# Central_MABOS.net
KiCad netlist of a schematic drawn in EAGLE
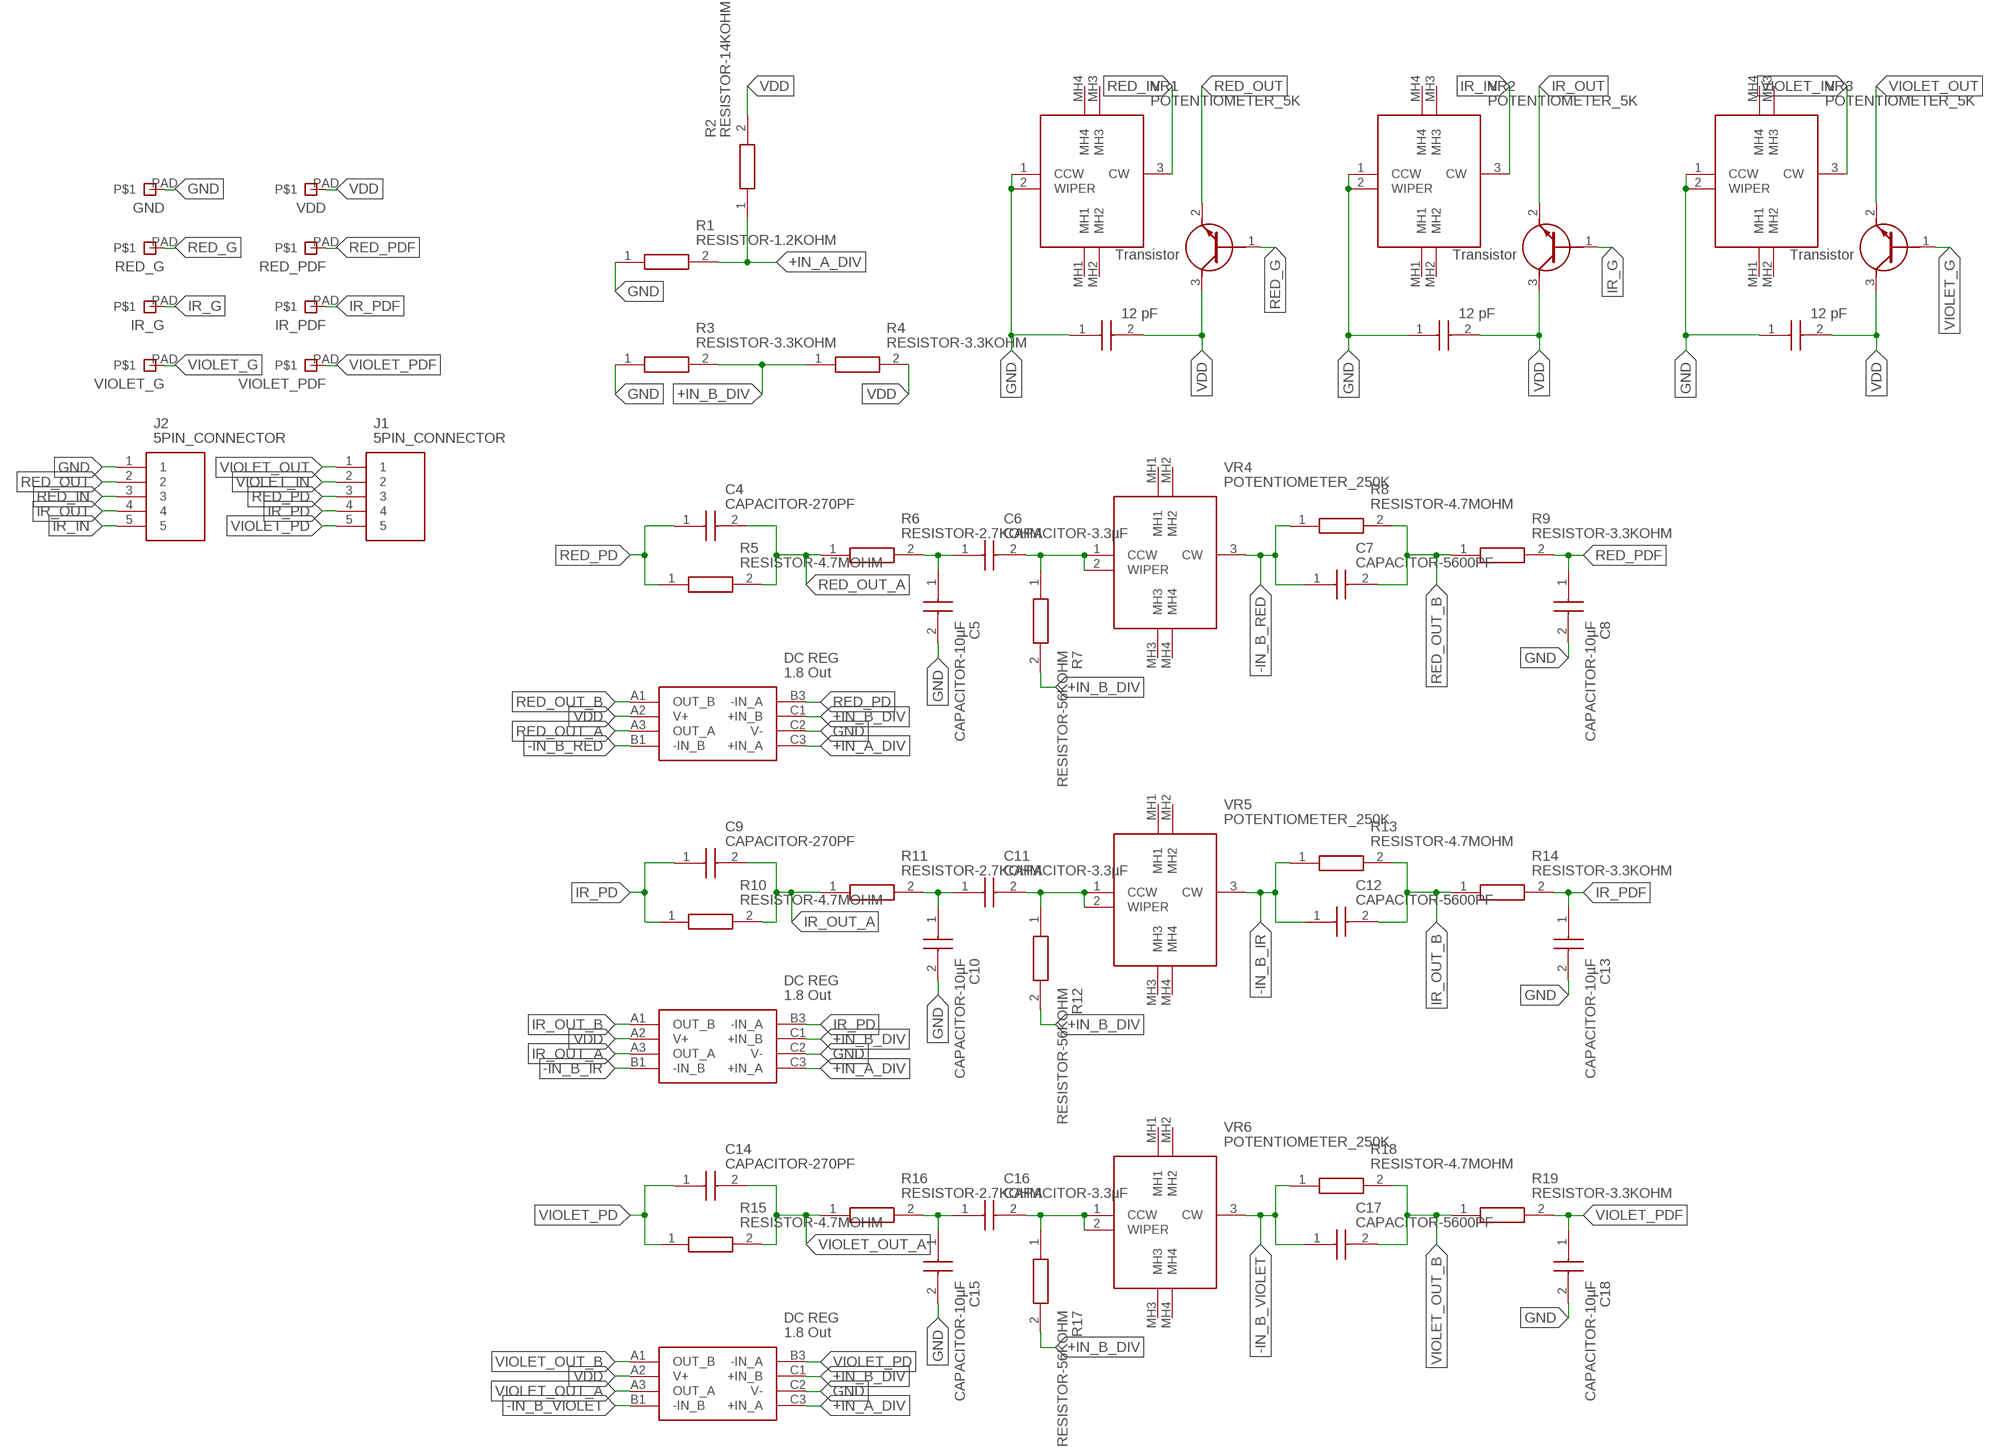
[diagram p0: schematic, sheet 1]

(export (version "E")
  (design (tool "Eeschema 10.0.6"))
  (components
    (comp (ref "C1")
      (value "CAPACITOR-12PF")
      (footprint "eagle-import:CAPC1005X55N")
      (fields
        (field (name "MANUFACTURER_PART_NUMBER") "C0402C120G3GACTU")
        (field (name "MOUSER_PART_NUMBER") "80-C0402C120G3G")
      )
      (libsource (lib "eagle-import") (part "CAPACITOR-12PF"))
    )
    (comp (ref "C2")
      (value "CAPACITOR-12PF")
      (footprint "eagle-import:CAPC1005X55N")
      (fields
        (field (name "MANUFACTURER_PART_NUMBER") "C0402C120G3GACTU")
        (field (name "MOUSER_PART_NUMBER") "80-C0402C120G3G")
      )
      (libsource (lib "eagle-import") (part "CAPACITOR-12PF"))
    )
    (comp (ref "C3")
      (value "CAPACITOR-12PF")
      (footprint "eagle-import:CAPC1005X55N")
      (fields
        (field (name "MANUFACTURER_PART_NUMBER") "C0402C120G3GACTU")
        (field (name "MOUSER_PART_NUMBER") "80-C0402C120G3G")
      )
      (libsource (lib "eagle-import") (part "CAPACITOR-12PF"))
    )
    (comp (ref "C4")
      (value "CAPACITOR-270PF")
      (footprint "eagle-import:CAPC1005X55N")
      (fields
        (field (name "MANUFACTURER_PART_NUMBER") "C0402C271G5GACTU")
        (field (name "MOUSER_PART_NUMBER") "80-C0402C271G5G")
      )
      (libsource (lib "eagle-import") (part "CAPACITOR-270PF"))
    )
    (comp (ref "C5")
      (value "CAPACITOR-10µF")
      (footprint "eagle-import:C0402")
      (fields
        (field (name "MANUFACTURER_PART_NUMBER") "C0402C106M9PACTU")
        (field (name "MOUSER_PART_NUMBER") "80-C0402C106M9P")
      )
      (libsource (lib "eagle-import") (part "CAPACITOR-10µF"))
    )
    (comp (ref "C6")
      (value "CAPACITOR-3.3µF")
      (footprint "eagle-import:C0402")
      (fields
        (field (name "MANUFACTURER_PART_NUMBER") "C0402C335M7PACTU")
        (field (name "MOUSER_PART_NUMBER") "80-C0402C335M7P")
      )
      (libsource (lib "eagle-import") (part "CAPACITOR-3.3µF"))
    )
    (comp (ref "C7")
      (value "CAPACITOR-5600PF")
      (footprint "eagle-import:CAPC1005X55N")
      (fields
        (field (name "MANUFACTURER_PART_NUMBER") "C0402C562J4RACTU")
        (field (name "MOUSER_PART_NUMBER") "80-C0402C562J4R")
      )
      (libsource (lib "eagle-import") (part "CAPACITOR-5600PF"))
    )
    (comp (ref "C8")
      (value "CAPACITOR-10µF")
      (footprint "eagle-import:C0402")
      (fields
        (field (name "MANUFACTURER_PART_NUMBER") "C0402C106M9PACTU")
        (field (name "MOUSER_PART_NUMBER") "80-C0402C106M9P")
      )
      (libsource (lib "eagle-import") (part "CAPACITOR-10µF"))
    )
    (comp (ref "C9")
      (value "CAPACITOR-270PF")
      (footprint "eagle-import:CAPC1005X55N")
      (fields
        (field (name "MANUFACTURER_PART_NUMBER") "C0402C271G5GACTU")
        (field (name "MOUSER_PART_NUMBER") "80-C0402C271G5G")
      )
      (libsource (lib "eagle-import") (part "CAPACITOR-270PF"))
    )
    (comp (ref "C10")
      (value "CAPACITOR-10µF")
      (footprint "eagle-import:C0402")
      (fields
        (field (name "MANUFACTURER_PART_NUMBER") "C0402C106M9PACTU")
        (field (name "MOUSER_PART_NUMBER") "80-C0402C106M9P")
      )
      (libsource (lib "eagle-import") (part "CAPACITOR-10µF"))
    )
    (comp (ref "C11")
      (value "CAPACITOR-3.3µF")
      (footprint "eagle-import:C0402")
      (fields
        (field (name "MANUFACTURER_PART_NUMBER") "C0402C335M7PACTU")
        (field (name "MOUSER_PART_NUMBER") "80-C0402C335M7P")
      )
      (libsource (lib "eagle-import") (part "CAPACITOR-3.3µF"))
    )
    (comp (ref "C12")
      (value "CAPACITOR-5600PF")
      (footprint "eagle-import:CAPC1005X55N")
      (fields
        (field (name "MANUFACTURER_PART_NUMBER") "C0402C562J4RACTU")
        (field (name "MOUSER_PART_NUMBER") "80-C0402C562J4R")
      )
      (libsource (lib "eagle-import") (part "CAPACITOR-5600PF"))
    )
    (comp (ref "C13")
      (value "CAPACITOR-10µF")
      (footprint "eagle-import:C0402")
      (fields
        (field (name "MANUFACTURER_PART_NUMBER") "C0402C106M9PACTU")
        (field (name "MOUSER_PART_NUMBER") "80-C0402C106M9P")
      )
      (libsource (lib "eagle-import") (part "CAPACITOR-10µF"))
    )
    (comp (ref "C14")
      (value "CAPACITOR-270PF")
      (footprint "eagle-import:CAPC1005X55N")
      (fields
        (field (name "MANUFACTURER_PART_NUMBER") "C0402C271G5GACTU")
        (field (name "MOUSER_PART_NUMBER") "80-C0402C271G5G")
      )
      (libsource (lib "eagle-import") (part "CAPACITOR-270PF"))
    )
    (comp (ref "C15")
      (value "CAPACITOR-10µF")
      (footprint "eagle-import:C0402")
      (fields
        (field (name "MANUFACTURER_PART_NUMBER") "C0402C106M9PACTU")
        (field (name "MOUSER_PART_NUMBER") "80-C0402C106M9P")
      )
      (libsource (lib "eagle-import") (part "CAPACITOR-10µF"))
    )
    (comp (ref "C16")
      (value "CAPACITOR-3.3µF")
      (footprint "eagle-import:C0402")
      (fields
        (field (name "MANUFACTURER_PART_NUMBER") "C0402C335M7PACTU")
        (field (name "MOUSER_PART_NUMBER") "80-C0402C335M7P")
      )
      (libsource (lib "eagle-import") (part "CAPACITOR-3.3µF"))
    )
    (comp (ref "C17")
      (value "CAPACITOR-5600PF")
      (footprint "eagle-import:CAPC1005X55N")
      (fields
        (field (name "MANUFACTURER_PART_NUMBER") "C0402C562J4RACTU")
        (field (name "MOUSER_PART_NUMBER") "80-C0402C562J4R")
      )
      (libsource (lib "eagle-import") (part "CAPACITOR-5600PF"))
    )
    (comp (ref "C18")
      (value "CAPACITOR-10µF")
      (footprint "eagle-import:C0402")
      (fields
        (field (name "MANUFACTURER_PART_NUMBER") "C0402C106M9PACTU")
        (field (name "MOUSER_PART_NUMBER") "80-C0402C106M9P")
      )
      (libsource (lib "eagle-import") (part "CAPACITOR-10µF"))
    )
    (comp (ref "GND")
      (value "PAD")
      (footprint "eagle-import:PAD")
      (libsource (lib "eagle-import") (part "PAD"))
    )
    (comp (ref "IC1")
      (value "ADA4505-2")
      (footprint "eagle-import:BGA8C50P3X3_142X142X65")
      (fields
        (field (name "MANUFACTURER_PART_NUMBER") "ADA4505-2ACBZ-R7")
        (field (name "MOUSER_PART_NUMBER") "584-ADA4505-2ACBZ-R7")
      )
      (libsource (lib "eagle-import") (part "ADA4505-2"))
    )
    (comp (ref "IC2")
      (value "ADA4505-2")
      (footprint "eagle-import:BGA8C50P3X3_142X142X65")
      (fields
        (field (name "MANUFACTURER_PART_NUMBER") "ADA4505-2ACBZ-R7")
        (field (name "MOUSER_PART_NUMBER") "584-ADA4505-2ACBZ-R7")
      )
      (libsource (lib "eagle-import") (part "ADA4505-2"))
    )
    (comp (ref "IC3")
      (value "ADA4505-2")
      (footprint "eagle-import:BGA8C50P3X3_142X142X65")
      (fields
        (field (name "MANUFACTURER_PART_NUMBER") "ADA4505-2ACBZ-R7")
        (field (name "MOUSER_PART_NUMBER") "584-ADA4505-2ACBZ-R7")
      )
      (libsource (lib "eagle-import") (part "ADA4505-2"))
    )
    (comp (ref "IR_G")
      (value "PAD")
      (footprint "eagle-import:PAD")
      (libsource (lib "eagle-import") (part "PAD"))
    )
    (comp (ref "IR_PDF")
      (value "PAD")
      (footprint "eagle-import:PAD")
      (libsource (lib "eagle-import") (part "PAD"))
    )
    (comp (ref "J1")
      (value "5PIN_CONNECTOR")
      (footprint "eagle-import:SHDR5W114P0X419_1X5_2228X658X1")
      (fields
        (field (name "MANUFACTURER_PART_NUMBER") "IPBT-105-H1-T-S-K")
        (field (name "MOUSER_PART_NUMBER") "200-IPBT105H1TSK")
      )
      (libsource (lib "eagle-import") (part "5PIN_CONNECTOR"))
    )
    (comp (ref "J2")
      (value "5PIN_CONNECTOR")
      (footprint "eagle-import:SHDR5W114P0X419_1X5_2228X658X1")
      (fields
        (field (name "MANUFACTURER_PART_NUMBER") "IPBT-105-H1-T-S-K")
        (field (name "MOUSER_PART_NUMBER") "200-IPBT105H1TSK")
      )
      (libsource (lib "eagle-import") (part "5PIN_CONNECTOR"))
    )
    (comp (ref "Q1")
      (value "TRANSISTOR")
      (footprint "eagle-import:SOT883B")
      (fields
        (field (name "MANUFACTURER_PART_NUMBER") "BC847BMB,315")
        (field (name "MOUSER_PART_NUMBER") "771-BC847BMB315")
      )
      (libsource (lib "eagle-import") (part "TRANSISTOR"))
    )
    (comp (ref "Q2")
      (value "TRANSISTOR")
      (footprint "eagle-import:SOT883B")
      (fields
        (field (name "MANUFACTURER_PART_NUMBER") "BC847BMB,315")
        (field (name "MOUSER_PART_NUMBER") "771-BC847BMB315")
      )
      (libsource (lib "eagle-import") (part "TRANSISTOR"))
    )
    (comp (ref "Q3")
      (value "TRANSISTOR")
      (footprint "eagle-import:SOT883B")
      (fields
        (field (name "MANUFACTURER_PART_NUMBER") "BC847BMB,315")
        (field (name "MOUSER_PART_NUMBER") "771-BC847BMB315")
      )
      (libsource (lib "eagle-import") (part "TRANSISTOR"))
    )
    (comp (ref "R1")
      (value "RESISTOR-1.2KOHM")
      (footprint "eagle-import:ERJPA2_(0402)")
      (fields
        (field (name "MANUFACTURER_PART_NUMBER") "ERJ-PA2D1201X")
        (field (name "MOUSER_PART_NUMBER") "667-ERJ-PA2D1201X")
      )
      (libsource (lib "eagle-import") (part "RESISTOR-1.2KOHM"))
    )
    (comp (ref "R2")
      (value "RESISTOR-14KOHM")
      (footprint "eagle-import:ERJ2RKD1004X")
      (fields
        (field (name "MANUFACTURER_PART_NUMBER") "ERJ-2RKF1402X")
        (field (name "MOUSER_PART_NUMBER") "667-ERJ-2RKF1402X")
      )
      (libsource (lib "eagle-import") (part "RESISTOR-14KOHM"))
    )
    (comp (ref "R3")
      (value "RESISTOR-3.3KOHM")
      (footprint "eagle-import:ERJPA2_(0402)")
      (fields
        (field (name "MANUFACTURER_PART_NUMBER") "ERJ-PA2F3301X")
        (field (name "MOUSER_PART_NUMBER") "667-ERJ-PA2F3301X")
      )
      (libsource (lib "eagle-import") (part "RESISTOR-3.3KOHM"))
    )
    (comp (ref "R4")
      (value "RESISTOR-3.3KOHM")
      (footprint "eagle-import:ERJPA2_(0402)")
      (fields
        (field (name "MANUFACTURER_PART_NUMBER") "ERJ-PA2F3301X")
        (field (name "MOUSER_PART_NUMBER") "667-ERJ-PA2F3301X")
      )
      (libsource (lib "eagle-import") (part "RESISTOR-3.3KOHM"))
    )
    (comp (ref "R5")
      (value "RESISTOR-4.7MOHM")
      (footprint "eagle-import:ERJ2RKD1004X")
      (fields
        (field (name "MANUFACTURER_PART_NUMBER") "ERJ-2GEJ475X")
        (field (name "MOUSER_PART_NUMBER") "667-ERJ-2GEJ475X")
      )
      (libsource (lib "eagle-import") (part "RESISTOR-4.7MOHM"))
    )
    (comp (ref "R6")
      (value "RESISTOR-2.7KOHM")
      (footprint "eagle-import:ERJPA2_(0402)")
      (fields (field (name "MANUFACTURER_PART_NUMBER") "ERJ-PA2F2701X"))
      (libsource (lib "eagle-import") (part "RESISTOR-2.7KOHM"))
    )
    (comp (ref "R7")
      (value "RESISTOR-56KOHM")
      (footprint "eagle-import:ERJ2RKD1004X")
      (fields
        (field (name "MANUFACTURER_PART_NUMBER") "ERJ-2RKF5602X")
        (field (name "MOUSER_PART_NUMBER") "667-ERJ-2RKF5602X")
      )
      (libsource (lib "eagle-import") (part "RESISTOR-56KOHM"))
    )
    (comp (ref "R8")
      (value "RESISTOR-4.7MOHM")
      (footprint "eagle-import:ERJ2RKD1004X")
      (fields
        (field (name "MANUFACTURER_PART_NUMBER") "ERJ-2GEJ475X")
        (field (name "MOUSER_PART_NUMBER") "667-ERJ-2GEJ475X")
      )
      (libsource (lib "eagle-import") (part "RESISTOR-4.7MOHM"))
    )
    (comp (ref "R9")
      (value "RESISTOR-3.3KOHM")
      (footprint "eagle-import:ERJPA2_(0402)")
      (fields
        (field (name "MANUFACTURER_PART_NUMBER") "ERJ-PA2F3301X")
        (field (name "MOUSER_PART_NUMBER") "667-ERJ-PA2F3301X")
      )
      (libsource (lib "eagle-import") (part "RESISTOR-3.3KOHM"))
    )
    (comp (ref "R10")
      (value "RESISTOR-4.7MOHM")
      (footprint "eagle-import:ERJ2RKD1004X")
      (fields
        (field (name "MANUFACTURER_PART_NUMBER") "ERJ-2GEJ475X")
        (field (name "MOUSER_PART_NUMBER") "667-ERJ-2GEJ475X")
      )
      (libsource (lib "eagle-import") (part "RESISTOR-4.7MOHM"))
    )
    (comp (ref "R11")
      (value "RESISTOR-2.7KOHM")
      (footprint "eagle-import:ERJPA2_(0402)")
      (fields (field (name "MANUFACTURER_PART_NUMBER") "ERJ-PA2F2701X"))
      (libsource (lib "eagle-import") (part "RESISTOR-2.7KOHM"))
    )
    (comp (ref "R12")
      (value "RESISTOR-56KOHM")
      (footprint "eagle-import:ERJ2RKD1004X")
      (fields
        (field (name "MANUFACTURER_PART_NUMBER") "ERJ-2RKF5602X")
        (field (name "MOUSER_PART_NUMBER") "667-ERJ-2RKF5602X")
      )
      (libsource (lib "eagle-import") (part "RESISTOR-56KOHM"))
    )
    (comp (ref "R13")
      (value "RESISTOR-4.7MOHM")
      (footprint "eagle-import:ERJ2RKD1004X")
      (fields
        (field (name "MANUFACTURER_PART_NUMBER") "ERJ-2GEJ475X")
        (field (name "MOUSER_PART_NUMBER") "667-ERJ-2GEJ475X")
      )
      (libsource (lib "eagle-import") (part "RESISTOR-4.7MOHM"))
    )
    (comp (ref "R14")
      (value "RESISTOR-3.3KOHM")
      (footprint "eagle-import:ERJPA2_(0402)")
      (fields
        (field (name "MANUFACTURER_PART_NUMBER") "ERJ-PA2F3301X")
        (field (name "MOUSER_PART_NUMBER") "667-ERJ-PA2F3301X")
      )
      (libsource (lib "eagle-import") (part "RESISTOR-3.3KOHM"))
    )
    (comp (ref "R15")
      (value "RESISTOR-4.7MOHM")
      (footprint "eagle-import:ERJ2RKD1004X")
      (fields
        (field (name "MANUFACTURER_PART_NUMBER") "ERJ-2GEJ475X")
        (field (name "MOUSER_PART_NUMBER") "667-ERJ-2GEJ475X")
      )
      (libsource (lib "eagle-import") (part "RESISTOR-4.7MOHM"))
    )
    (comp (ref "R16")
      (value "RESISTOR-2.7KOHM")
      (footprint "eagle-import:ERJPA2_(0402)")
      (fields (field (name "MANUFACTURER_PART_NUMBER") "ERJ-PA2F2701X"))
      (libsource (lib "eagle-import") (part "RESISTOR-2.7KOHM"))
    )
    (comp (ref "R17")
      (value "RESISTOR-56KOHM")
      (footprint "eagle-import:ERJ2RKD1004X")
      (fields
        (field (name "MANUFACTURER_PART_NUMBER") "ERJ-2RKF5602X")
        (field (name "MOUSER_PART_NUMBER") "667-ERJ-2RKF5602X")
      )
      (libsource (lib "eagle-import") (part "RESISTOR-56KOHM"))
    )
    (comp (ref "R18")
      (value "RESISTOR-4.7MOHM")
      (footprint "eagle-import:ERJ2RKD1004X")
      (fields
        (field (name "MANUFACTURER_PART_NUMBER") "ERJ-2GEJ475X")
        (field (name "MOUSER_PART_NUMBER") "667-ERJ-2GEJ475X")
      )
      (libsource (lib "eagle-import") (part "RESISTOR-4.7MOHM"))
    )
    (comp (ref "R19")
      (value "RESISTOR-3.3KOHM")
      (footprint "eagle-import:ERJPA2_(0402)")
      (fields
        (field (name "MANUFACTURER_PART_NUMBER") "ERJ-PA2F3301X")
        (field (name "MOUSER_PART_NUMBER") "667-ERJ-PA2F3301X")
      )
      (libsource (lib "eagle-import") (part "RESISTOR-3.3KOHM"))
    )
    (comp (ref "RED_G")
      (value "PAD")
      (footprint "eagle-import:PAD")
      (libsource (lib "eagle-import") (part "PAD"))
    )
    (comp (ref "RED_PDF")
      (value "PAD")
      (footprint "eagle-import:PAD")
      (libsource (lib "eagle-import") (part "PAD"))
    )
    (comp (ref "VDD")
      (value "PAD")
      (footprint "eagle-import:PAD")
      (libsource (lib "eagle-import") (part "PAD"))
    )
    (comp (ref "VIOLET_G")
      (value "PAD")
      (footprint "eagle-import:PAD")
      (libsource (lib "eagle-import") (part "PAD"))
    )
    (comp (ref "VIOLET_PDF")
      (value "PAD")
      (footprint "eagle-import:PAD")
      (libsource (lib "eagle-import") (part "PAD"))
    )
    (comp (ref "VR1")
      (value "POTENTIOMETER_5K")
      (footprint "eagle-import:POTENTIOMETER")
      (fields
        (field (name "MANUFACTURER_PART_NUMBER") "PS15-10PC1BR5K")
        (field (name "MOUSER_PART_NUMBER") "858-PS1510PC1BR5K")
      )
      (libsource (lib "eagle-import") (part "POTENTIOMETER_5K"))
    )
    (comp (ref "VR2")
      (value "POTENTIOMETER_5K")
      (footprint "eagle-import:POTENTIOMETER")
      (fields
        (field (name "MANUFACTURER_PART_NUMBER") "PS15-10PC1BR5K")
        (field (name "MOUSER_PART_NUMBER") "858-PS1510PC1BR5K")
      )
      (libsource (lib "eagle-import") (part "POTENTIOMETER_5K"))
    )
    (comp (ref "VR3")
      (value "POTENTIOMETER_5K")
      (footprint "eagle-import:POTENTIOMETER")
      (fields
        (field (name "MANUFACTURER_PART_NUMBER") "PS15-10PC1BR5K")
        (field (name "MOUSER_PART_NUMBER") "858-PS1510PC1BR5K")
      )
      (libsource (lib "eagle-import") (part "POTENTIOMETER_5K"))
    )
    (comp (ref "VR4")
      (value "POTENTIOMETER_250K")
      (footprint "eagle-import:PTA60432015DPB254")
      (fields
        (field (name "MANUFACTURER_PART_NUMBER") "PTA6043-2015DPB254")
        (field (name "MOUSER_PART_NUMBER") "652-PTA6432015DPB254")
      )
      (libsource (lib "eagle-import") (part "POTENTIOMETER_250K"))
    )
    (comp (ref "VR5")
      (value "POTENTIOMETER_250K")
      (footprint "eagle-import:PTA60432015DPB254")
      (fields
        (field (name "MANUFACTURER_PART_NUMBER") "PTA6043-2015DPB254")
        (field (name "MOUSER_PART_NUMBER") "652-PTA6432015DPB254")
      )
      (libsource (lib "eagle-import") (part "POTENTIOMETER_250K"))
    )
    (comp (ref "VR6")
      (value "POTENTIOMETER_250K")
      (footprint "eagle-import:PTA60432015DPB254")
      (fields
        (field (name "MANUFACTURER_PART_NUMBER") "PTA6043-2015DPB254")
        (field (name "MOUSER_PART_NUMBER") "652-PTA6432015DPB254")
      )
      (libsource (lib "eagle-import") (part "POTENTIOMETER_250K"))
    )
  )
  (nets
    (net (code "1") (name "+IN_A_DIV") (class "Default")
      (node (ref "IC1") (pin "C3") (pinfunction "+IN_A_C3") (pintype "bidirectional"))
      (node (ref "IC2") (pin "C3") (pinfunction "+IN_A_C3") (pintype "bidirectional"))
      (node (ref "IC3") (pin "C3") (pinfunction "+IN_A_C3") (pintype "bidirectional"))
      (node (ref "R1") (pin "2") (pinfunction "2_2") (pintype "bidirectional"))
      (node (ref "R2") (pin "1") (pinfunction "1_1") (pintype "bidirectional"))
    )
    (net (code "2") (name "+IN_B_DIV") (class "Default")
      (node (ref "IC1") (pin "C1") (pinfunction "+IN_B_C1") (pintype "bidirectional"))
      (node (ref "IC2") (pin "C1") (pinfunction "+IN_B_C1") (pintype "bidirectional"))
      (node (ref "IC3") (pin "C1") (pinfunction "+IN_B_C1") (pintype "bidirectional"))
      (node (ref "R12") (pin "2") (pinfunction "2_2") (pintype "bidirectional"))
      (node (ref "R17") (pin "2") (pinfunction "2_2") (pintype "bidirectional"))
      (node (ref "R3") (pin "2") (pinfunction "2_2") (pintype "bidirectional"))
      (node (ref "R4") (pin "1") (pinfunction "1_1") (pintype "bidirectional"))
      (node (ref "R7") (pin "2") (pinfunction "2_2") (pintype "bidirectional"))
    )
    (net (code "3") (name "-IN_B_IR") (class "Default")
      (node (ref "C12") (pin "1") (pinfunction "1_1") (pintype "bidirectional"))
      (node (ref "IC2") (pin "B1") (pinfunction "-IN_B_B1") (pintype "bidirectional"))
      (node (ref "R13") (pin "1") (pinfunction "1_1") (pintype "bidirectional"))
      (node (ref "VR5") (pin "3") (pinfunction "CW_3") (pintype "bidirectional"))
    )
    (net (code "4") (name "-IN_B_RED") (class "Default")
      (node (ref "C7") (pin "1") (pinfunction "1_1") (pintype "bidirectional"))
      (node (ref "IC1") (pin "B1") (pinfunction "-IN_B_B1") (pintype "bidirectional"))
      (node (ref "R8") (pin "1") (pinfunction "1_1") (pintype "bidirectional"))
      (node (ref "VR4") (pin "3") (pinfunction "CW_3") (pintype "bidirectional"))
    )
    (net (code "5") (name "-IN_B_VIOLET") (class "Default")
      (node (ref "C17") (pin "1") (pinfunction "1_1") (pintype "bidirectional"))
      (node (ref "IC3") (pin "B1") (pinfunction "-IN_B_B1") (pintype "bidirectional"))
      (node (ref "R18") (pin "1") (pinfunction "1_1") (pintype "bidirectional"))
      (node (ref "VR6") (pin "3") (pinfunction "CW_3") (pintype "bidirectional"))
    )
    (net (code "6") (name "GND") (class "Default")
      (node (ref "C1") (pin "1") (pinfunction "1_1") (pintype "bidirectional"))
      (node (ref "C10") (pin "2") (pinfunction "2_2") (pintype "bidirectional"))
      (node (ref "C13") (pin "2") (pinfunction "2_2") (pintype "bidirectional"))
      (node (ref "C15") (pin "2") (pinfunction "2_2") (pintype "bidirectional"))
      (node (ref "C18") (pin "2") (pinfunction "2_2") (pintype "bidirectional"))
      (node (ref "C2") (pin "1") (pinfunction "1_1") (pintype "bidirectional"))
      (node (ref "C3") (pin "1") (pinfunction "1_1") (pintype "bidirectional"))
      (node (ref "C5") (pin "2") (pinfunction "2_2") (pintype "bidirectional"))
      (node (ref "C8") (pin "2") (pinfunction "2_2") (pintype "bidirectional"))
      (node (ref "GND") (pin "PAD") (pinfunction "P$1_PAD") (pintype "bidirectional"))
      (node (ref "IC1") (pin "C2") (pinfunction "V-_C2") (pintype "bidirectional"))
      (node (ref "IC2") (pin "C2") (pinfunction "V-_C2") (pintype "bidirectional"))
      (node (ref "IC3") (pin "C2") (pinfunction "V-_C2") (pintype "bidirectional"))
      (node (ref "J2") (pin "1") (pinfunction "1_1") (pintype "bidirectional"))
      (node (ref "R1") (pin "1") (pinfunction "1_1") (pintype "bidirectional"))
      (node (ref "R3") (pin "1") (pinfunction "1_1") (pintype "bidirectional"))
      (node (ref "VR1") (pin "1") (pinfunction "CCW_1") (pintype "bidirectional"))
      (node (ref "VR1") (pin "2") (pinfunction "WIPER_2") (pintype "bidirectional"))
      (node (ref "VR2") (pin "1") (pinfunction "CCW_1") (pintype "bidirectional"))
      (node (ref "VR2") (pin "2") (pinfunction "WIPER_2") (pintype "bidirectional"))
      (node (ref "VR3") (pin "1") (pinfunction "CCW_1") (pintype "bidirectional"))
      (node (ref "VR3") (pin "2") (pinfunction "WIPER_2") (pintype "bidirectional"))
    )
    (net (code "7") (name "IR_G") (class "Default")
      (node (ref "IR_G") (pin "PAD") (pinfunction "P$1_PAD") (pintype "bidirectional"))
      (node (ref "Q2") (pin "1") (pinfunction "B_1") (pintype "bidirectional"))
    )
    (net (code "8") (name "IR_IN") (class "Default")
      (node (ref "J2") (pin "5") (pinfunction "5_5") (pintype "bidirectional"))
      (node (ref "VR2") (pin "3") (pinfunction "CW_3") (pintype "bidirectional"))
    )
    (net (code "9") (name "IR_OUT") (class "Default")
      (node (ref "J2") (pin "4") (pinfunction "4_4") (pintype "bidirectional"))
      (node (ref "Q2") (pin "2") (pinfunction "E_2") (pintype "bidirectional"))
    )
    (net (code "10") (name "IR_OUT_A") (class "Default")
      (node (ref "C9") (pin "2") (pinfunction "2_2") (pintype "bidirectional"))
      (node (ref "IC2") (pin "A3") (pinfunction "OUT_A_A3") (pintype "bidirectional"))
      (node (ref "R10") (pin "2") (pinfunction "2_2") (pintype "bidirectional"))
      (node (ref "R11") (pin "1") (pinfunction "1_1") (pintype "bidirectional"))
    )
    (net (code "11") (name "IR_OUT_B") (class "Default")
      (node (ref "C12") (pin "2") (pinfunction "2_2") (pintype "bidirectional"))
      (node (ref "IC2") (pin "A1") (pinfunction "OUT_B_A1") (pintype "bidirectional"))
      (node (ref "R13") (pin "2") (pinfunction "2_2") (pintype "bidirectional"))
      (node (ref "R14") (pin "1") (pinfunction "1_1") (pintype "bidirectional"))
    )
    (net (code "12") (name "IR_PD") (class "Default")
      (node (ref "C9") (pin "1") (pinfunction "1_1") (pintype "bidirectional"))
      (node (ref "IC2") (pin "B3") (pinfunction "-IN_A_B3") (pintype "bidirectional"))
      (node (ref "J1") (pin "4") (pinfunction "4_4") (pintype "bidirectional"))
      (node (ref "R10") (pin "1") (pinfunction "1_1") (pintype "bidirectional"))
    )
    (net (code "13") (name "IR_PDF") (class "Default")
      (node (ref "C13") (pin "1") (pinfunction "1_1") (pintype "bidirectional"))
      (node (ref "IR_PDF") (pin "PAD") (pinfunction "P$1_PAD") (pintype "bidirectional"))
      (node (ref "R14") (pin "2") (pinfunction "2_2") (pintype "bidirectional"))
    )
    (net (code "14") (name "Net-(C5-Pad1)") (class "Default")
      (node (ref "C5") (pin "1") (pinfunction "1_1") (pintype "bidirectional"))
      (node (ref "C6") (pin "1") (pinfunction "1_1") (pintype "bidirectional"))
      (node (ref "R6") (pin "2") (pinfunction "2_2") (pintype "bidirectional"))
    )
    (net (code "15") (name "Net-(C10-Pad1)") (class "Default")
      (node (ref "C10") (pin "1") (pinfunction "1_1") (pintype "bidirectional"))
      (node (ref "C11") (pin "1") (pinfunction "1_1") (pintype "bidirectional"))
      (node (ref "R11") (pin "2") (pinfunction "2_2") (pintype "bidirectional"))
    )
    (net (code "16") (name "Net-(C15-Pad1)") (class "Default")
      (node (ref "C15") (pin "1") (pinfunction "1_1") (pintype "bidirectional"))
      (node (ref "C16") (pin "1") (pinfunction "1_1") (pintype "bidirectional"))
      (node (ref "R16") (pin "2") (pinfunction "2_2") (pintype "bidirectional"))
    )
    (net (code "17") (name "Net-(VR4-CCW)") (class "Default")
      (node (ref "C6") (pin "2") (pinfunction "2_2") (pintype "bidirectional"))
      (node (ref "R7") (pin "1") (pinfunction "1_1") (pintype "bidirectional"))
      (node (ref "VR4") (pin "1") (pinfunction "CCW_1") (pintype "bidirectional"))
      (node (ref "VR4") (pin "2") (pinfunction "WIPER_2") (pintype "bidirectional"))
    )
    (net (code "18") (name "Net-(VR5-CCW)") (class "Default")
      (node (ref "C11") (pin "2") (pinfunction "2_2") (pintype "bidirectional"))
      (node (ref "R12") (pin "1") (pinfunction "1_1") (pintype "bidirectional"))
      (node (ref "VR5") (pin "1") (pinfunction "CCW_1") (pintype "bidirectional"))
      (node (ref "VR5") (pin "2") (pinfunction "WIPER_2") (pintype "bidirectional"))
    )
    (net (code "19") (name "Net-(VR6-CCW)") (class "Default")
      (node (ref "C16") (pin "2") (pinfunction "2_2") (pintype "bidirectional"))
      (node (ref "R17") (pin "1") (pinfunction "1_1") (pintype "bidirectional"))
      (node (ref "VR6") (pin "1") (pinfunction "CCW_1") (pintype "bidirectional"))
      (node (ref "VR6") (pin "2") (pinfunction "WIPER_2") (pintype "bidirectional"))
    )
    (net (code "20") (name "RED_G") (class "Default")
      (node (ref "Q1") (pin "1") (pinfunction "B_1") (pintype "bidirectional"))
      (node (ref "RED_G") (pin "PAD") (pinfunction "P$1_PAD") (pintype "bidirectional"))
    )
    (net (code "21") (name "RED_IN") (class "Default")
      (node (ref "J2") (pin "3") (pinfunction "3_3") (pintype "bidirectional"))
      (node (ref "VR1") (pin "3") (pinfunction "CW_3") (pintype "bidirectional"))
    )
    (net (code "22") (name "RED_OUT") (class "Default")
      (node (ref "J2") (pin "2") (pinfunction "2_2") (pintype "bidirectional"))
      (node (ref "Q1") (pin "2") (pinfunction "E_2") (pintype "bidirectional"))
    )
    (net (code "23") (name "RED_OUT_A") (class "Default")
      (node (ref "C4") (pin "2") (pinfunction "2_2") (pintype "bidirectional"))
      (node (ref "IC1") (pin "A3") (pinfunction "OUT_A_A3") (pintype "bidirectional"))
      (node (ref "R5") (pin "2") (pinfunction "2_2") (pintype "bidirectional"))
      (node (ref "R6") (pin "1") (pinfunction "1_1") (pintype "bidirectional"))
    )
    (net (code "24") (name "RED_OUT_B") (class "Default")
      (node (ref "C7") (pin "2") (pinfunction "2_2") (pintype "bidirectional"))
      (node (ref "IC1") (pin "A1") (pinfunction "OUT_B_A1") (pintype "bidirectional"))
      (node (ref "R8") (pin "2") (pinfunction "2_2") (pintype "bidirectional"))
      (node (ref "R9") (pin "1") (pinfunction "1_1") (pintype "bidirectional"))
    )
    (net (code "25") (name "RED_PD") (class "Default")
      (node (ref "C4") (pin "1") (pinfunction "1_1") (pintype "bidirectional"))
      (node (ref "IC1") (pin "B3") (pinfunction "-IN_A_B3") (pintype "bidirectional"))
      (node (ref "J1") (pin "3") (pinfunction "3_3") (pintype "bidirectional"))
      (node (ref "R5") (pin "1") (pinfunction "1_1") (pintype "bidirectional"))
    )
    (net (code "26") (name "RED_PDF") (class "Default")
      (node (ref "C8") (pin "1") (pinfunction "1_1") (pintype "bidirectional"))
      (node (ref "R9") (pin "2") (pinfunction "2_2") (pintype "bidirectional"))
      (node (ref "RED_PDF") (pin "PAD") (pinfunction "P$1_PAD") (pintype "bidirectional"))
    )
    (net (code "27") (name "VDD") (class "Default")
      (node (ref "C1") (pin "2") (pinfunction "2_2") (pintype "bidirectional"))
      (node (ref "C2") (pin "2") (pinfunction "2_2") (pintype "bidirectional"))
      (node (ref "C3") (pin "2") (pinfunction "2_2") (pintype "bidirectional"))
      (node (ref "IC1") (pin "A2") (pinfunction "V+_A2") (pintype "bidirectional"))
      (node (ref "IC2") (pin "A2") (pinfunction "V+_A2") (pintype "bidirectional"))
      (node (ref "IC3") (pin "A2") (pinfunction "V+_A2") (pintype "bidirectional"))
      (node (ref "Q1") (pin "3") (pinfunction "C_3") (pintype "bidirectional"))
      (node (ref "Q2") (pin "3") (pinfunction "C_3") (pintype "bidirectional"))
      (node (ref "Q3") (pin "3") (pinfunction "C_3") (pintype "bidirectional"))
      (node (ref "R2") (pin "2") (pinfunction "2_2") (pintype "bidirectional"))
      (node (ref "R4") (pin "2") (pinfunction "2_2") (pintype "bidirectional"))
      (node (ref "VDD") (pin "PAD") (pinfunction "P$1_PAD") (pintype "bidirectional"))
    )
    (net (code "28") (name "VIOLET_G") (class "Default")
      (node (ref "Q3") (pin "1") (pinfunction "B_1") (pintype "bidirectional"))
      (node (ref "VIOLET_G") (pin "PAD") (pinfunction "P$1_PAD") (pintype "bidirectional"))
    )
    (net (code "29") (name "VIOLET_IN") (class "Default")
      (node (ref "J1") (pin "2") (pinfunction "2_2") (pintype "bidirectional"))
      (node (ref "VR3") (pin "3") (pinfunction "CW_3") (pintype "bidirectional"))
    )
    (net (code "30") (name "VIOLET_OUT") (class "Default")
      (node (ref "J1") (pin "1") (pinfunction "1_1") (pintype "bidirectional"))
      (node (ref "Q3") (pin "2") (pinfunction "E_2") (pintype "bidirectional"))
    )
    (net (code "31") (name "VIOLET_OUT_A") (class "Default")
      (node (ref "C14") (pin "2") (pinfunction "2_2") (pintype "bidirectional"))
      (node (ref "IC3") (pin "A3") (pinfunction "OUT_A_A3") (pintype "bidirectional"))
      (node (ref "R15") (pin "2") (pinfunction "2_2") (pintype "bidirectional"))
      (node (ref "R16") (pin "1") (pinfunction "1_1") (pintype "bidirectional"))
    )
    (net (code "32") (name "VIOLET_OUT_B") (class "Default")
      (node (ref "C17") (pin "2") (pinfunction "2_2") (pintype "bidirectional"))
      (node (ref "IC3") (pin "A1") (pinfunction "OUT_B_A1") (pintype "bidirectional"))
      (node (ref "R18") (pin "2") (pinfunction "2_2") (pintype "bidirectional"))
      (node (ref "R19") (pin "1") (pinfunction "1_1") (pintype "bidirectional"))
    )
    (net (code "33") (name "VIOLET_PD") (class "Default")
      (node (ref "C14") (pin "1") (pinfunction "1_1") (pintype "bidirectional"))
      (node (ref "IC3") (pin "B3") (pinfunction "-IN_A_B3") (pintype "bidirectional"))
      (node (ref "J1") (pin "5") (pinfunction "5_5") (pintype "bidirectional"))
      (node (ref "R15") (pin "1") (pinfunction "1_1") (pintype "bidirectional"))
    )
    (net (code "34") (name "VIOLET_PDF") (class "Default")
      (node (ref "C18") (pin "1") (pinfunction "1_1") (pintype "bidirectional"))
      (node (ref "R19") (pin "2") (pinfunction "2_2") (pintype "bidirectional"))
      (node (ref "VIOLET_PDF") (pin "PAD") (pinfunction "P$1_PAD") (pintype "bidirectional"))
    )
    (net (code "35") (name "unconnected-(VR1-PadMH1)") (class "Default")
      (node (ref "VR1") (pin "MH1") (pinfunction "MH1_MH1") (pintype "bidirectional"))
    )
    (net (code "36") (name "unconnected-(VR1-PadMH2)") (class "Default")
      (node (ref "VR1") (pin "MH2") (pinfunction "MH2_MH2") (pintype "bidirectional"))
    )
    (net (code "37") (name "unconnected-(VR1-PadMH3)") (class "Default")
      (node (ref "VR1") (pin "MH3") (pinfunction "MH3_MH3") (pintype "bidirectional"))
    )
    (net (code "38") (name "unconnected-(VR1-PadMH4)") (class "Default")
      (node (ref "VR1") (pin "MH4") (pinfunction "MH4_MH4") (pintype "bidirectional"))
    )
    (net (code "39") (name "unconnected-(VR2-PadMH1)") (class "Default")
      (node (ref "VR2") (pin "MH1") (pinfunction "MH1_MH1") (pintype "bidirectional"))
    )
    (net (code "40") (name "unconnected-(VR2-PadMH2)") (class "Default")
      (node (ref "VR2") (pin "MH2") (pinfunction "MH2_MH2") (pintype "bidirectional"))
    )
    (net (code "41") (name "unconnected-(VR2-PadMH3)") (class "Default")
      (node (ref "VR2") (pin "MH3") (pinfunction "MH3_MH3") (pintype "bidirectional"))
    )
    (net (code "42") (name "unconnected-(VR2-PadMH4)") (class "Default")
      (node (ref "VR2") (pin "MH4") (pinfunction "MH4_MH4") (pintype "bidirectional"))
    )
    (net (code "43") (name "unconnected-(VR3-PadMH1)") (class "Default")
      (node (ref "VR3") (pin "MH1") (pinfunction "MH1_MH1") (pintype "bidirectional"))
    )
    (net (code "44") (name "unconnected-(VR3-PadMH2)") (class "Default")
      (node (ref "VR3") (pin "MH2") (pinfunction "MH2_MH2") (pintype "bidirectional"))
    )
    (net (code "45") (name "unconnected-(VR3-PadMH3)") (class "Default")
      (node (ref "VR3") (pin "MH3") (pinfunction "MH3_MH3") (pintype "bidirectional"))
    )
    (net (code "46") (name "unconnected-(VR3-PadMH4)") (class "Default")
      (node (ref "VR3") (pin "MH4") (pinfunction "MH4_MH4") (pintype "bidirectional"))
    )
    (net (code "47") (name "unconnected-(VR4-PadMH1)") (class "Default")
      (node (ref "VR4") (pin "MH1") (pinfunction "MH1_MH1") (pintype "bidirectional"))
    )
    (net (code "48") (name "unconnected-(VR4-PadMH2)") (class "Default")
      (node (ref "VR4") (pin "MH2") (pinfunction "MH2_MH2") (pintype "bidirectional"))
    )
    (net (code "49") (name "unconnected-(VR4-PadMH3)") (class "Default")
      (node (ref "VR4") (pin "MH3") (pinfunction "MH3_MH3") (pintype "bidirectional"))
    )
    (net (code "50") (name "unconnected-(VR4-PadMH4)") (class "Default")
      (node (ref "VR4") (pin "MH4") (pinfunction "MH4_MH4") (pintype "bidirectional"))
    )
    (net (code "51") (name "unconnected-(VR5-PadMH1)") (class "Default")
      (node (ref "VR5") (pin "MH1") (pinfunction "MH1_MH1") (pintype "bidirectional"))
    )
    (net (code "52") (name "unconnected-(VR5-PadMH2)") (class "Default")
      (node (ref "VR5") (pin "MH2") (pinfunction "MH2_MH2") (pintype "bidirectional"))
    )
    (net (code "53") (name "unconnected-(VR5-PadMH3)") (class "Default")
      (node (ref "VR5") (pin "MH3") (pinfunction "MH3_MH3") (pintype "bidirectional"))
    )
    (net (code "54") (name "unconnected-(VR5-PadMH4)") (class "Default")
      (node (ref "VR5") (pin "MH4") (pinfunction "MH4_MH4") (pintype "bidirectional"))
    )
    (net (code "55") (name "unconnected-(VR6-PadMH1)") (class "Default")
      (node (ref "VR6") (pin "MH1") (pinfunction "MH1_MH1") (pintype "bidirectional"))
    )
    (net (code "56") (name "unconnected-(VR6-PadMH2)") (class "Default")
      (node (ref "VR6") (pin "MH2") (pinfunction "MH2_MH2") (pintype "bidirectional"))
    )
    (net (code "57") (name "unconnected-(VR6-PadMH3)") (class "Default")
      (node (ref "VR6") (pin "MH3") (pinfunction "MH3_MH3") (pintype "bidirectional"))
    )
    (net (code "58") (name "unconnected-(VR6-PadMH4)") (class "Default")
      (node (ref "VR6") (pin "MH4") (pinfunction "MH4_MH4") (pintype "bidirectional"))
    )
  )
)
